# attiny_batsense.net
KiCad netlist of a schematic drawn in EAGLE
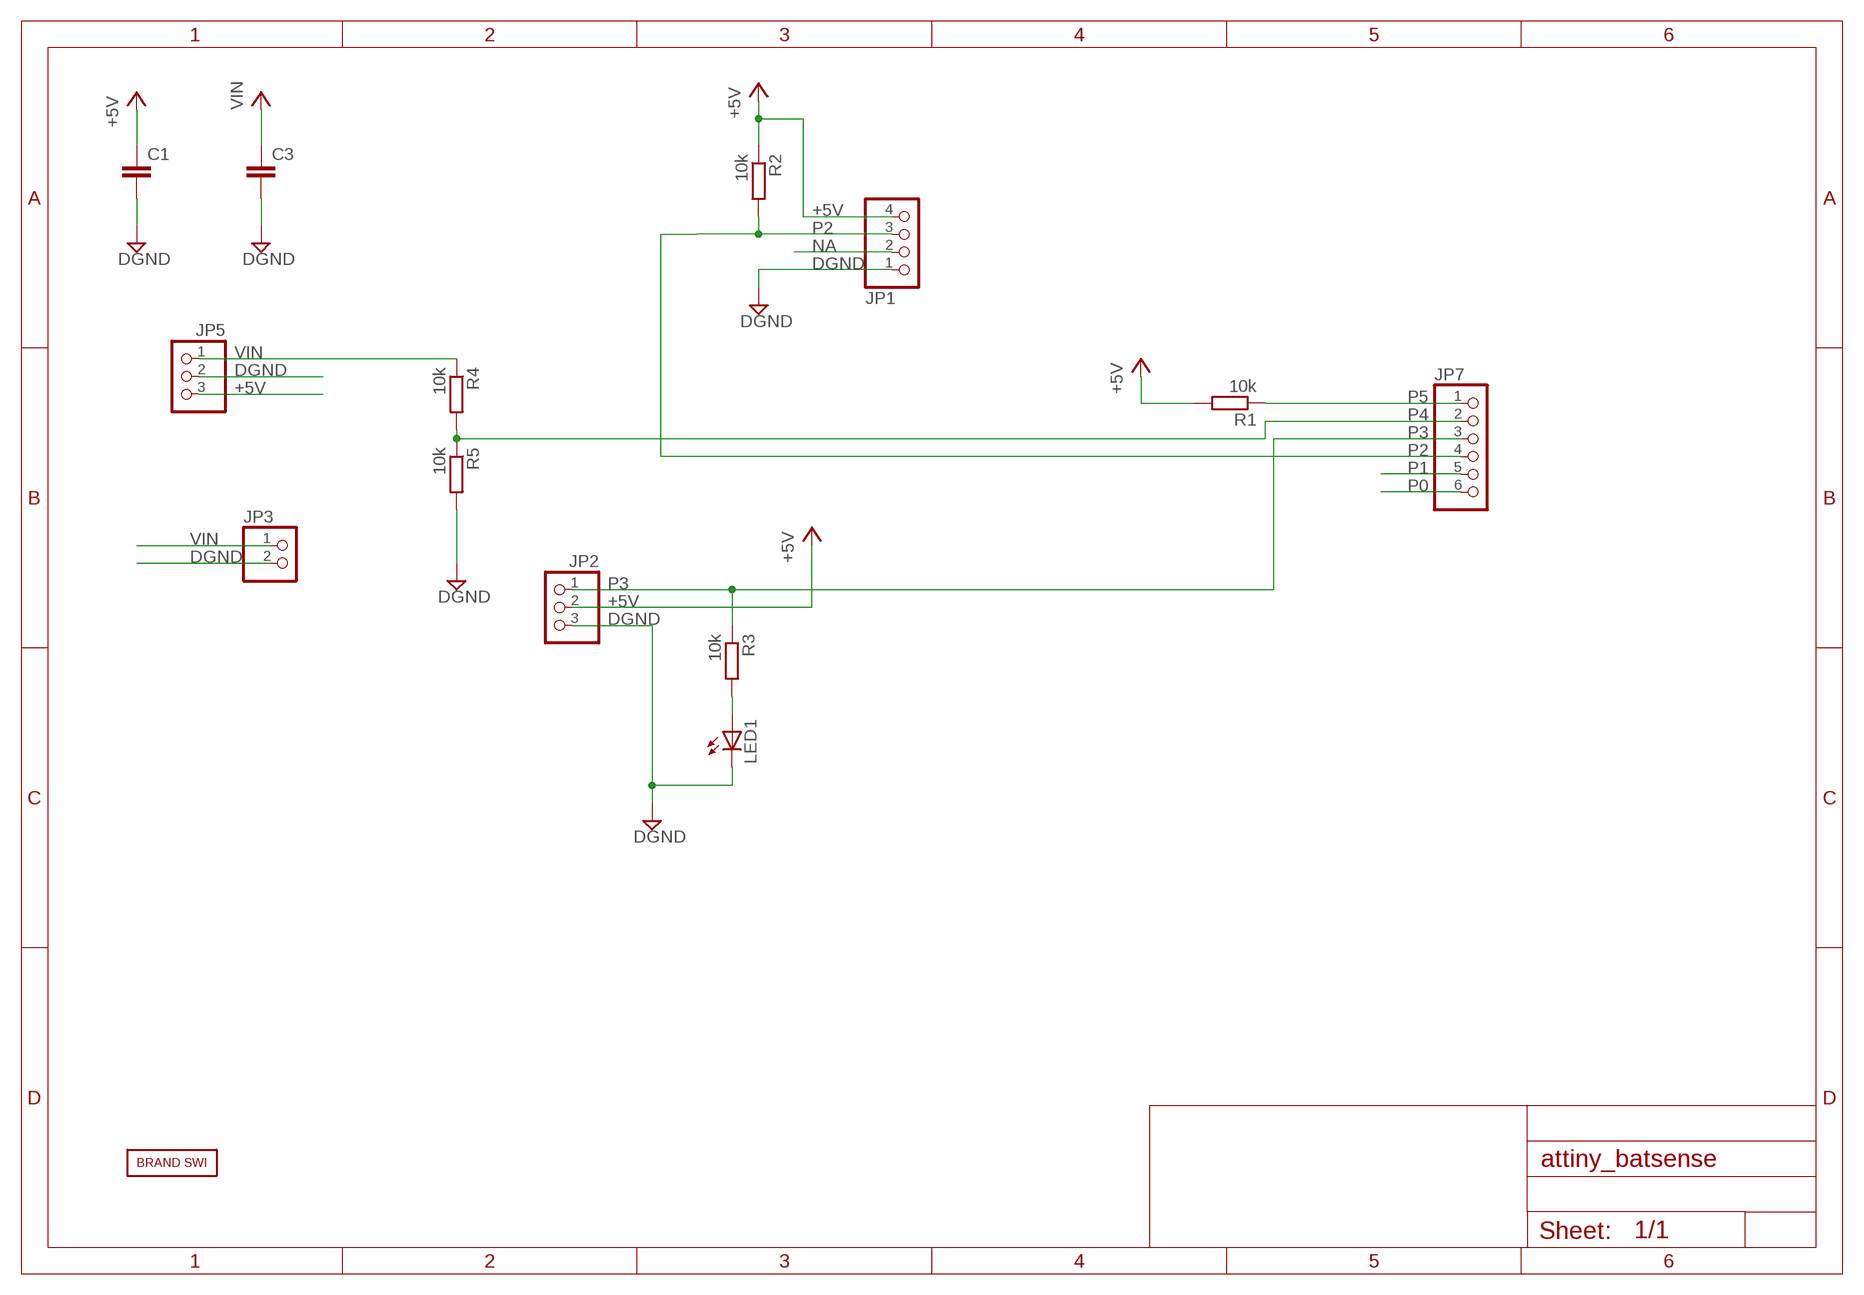
[diagram p0: schematic, sheet 1]

(export (version "E")
  (design (tool "Eeschema 10.0.6"))
  (components
    (comp (ref "C1")
      (value "C-EUC1210")
      (footprint "eagle-import:C1210")
      (libsource (lib "eagle-import") (part "C-EUC1210"))
    )
    (comp (ref "C3")
      (value "C-EUC1210")
      (footprint "eagle-import:C1210")
      (libsource (lib "eagle-import") (part "C-EUC1210"))
    )
    (comp (ref "JP1")
      (value "PINHD-1X4")
      (footprint "eagle-import:1X04")
      (libsource (lib "eagle-import") (part "PINHD-1X4"))
    )
    (comp (ref "JP2")
      (value "PINHD-1X3")
      (footprint "eagle-import:1X03")
      (libsource (lib "eagle-import") (part "PINHD-1X3"))
    )
    (comp (ref "JP3")
      (value "PINHD-1X2")
      (footprint "eagle-import:1X02")
      (libsource (lib "eagle-import") (part "PINHD-1X2"))
    )
    (comp (ref "JP5")
      (value "PINHD-1X3")
      (footprint "eagle-import:1X03")
      (libsource (lib "eagle-import") (part "PINHD-1X3"))
    )
    (comp (ref "JP7")
      (value "PINHD-1X6")
      (footprint "eagle-import:1X06")
      (libsource (lib "eagle-import") (part "PINHD-1X6"))
    )
    (comp (ref "LED1")
      (value "LED3MM")
      (footprint "eagle-import:LED3MM")
      (libsource (lib "eagle-import") (part "LED3MM"))
    )
    (comp (ref "R1")
      (value "10k")
      (footprint "eagle-import:R0805")
      (libsource (lib "eagle-import") (part "R-EU_R0805"))
    )
    (comp (ref "R2")
      (value "10k")
      (footprint "eagle-import:R0805")
      (libsource (lib "eagle-import") (part "R-EU_R0805"))
    )
    (comp (ref "R3")
      (value "10k")
      (footprint "eagle-import:R0805")
      (libsource (lib "eagle-import") (part "R-EU_R0805"))
    )
    (comp (ref "R4")
      (value "10k")
      (footprint "eagle-import:R0805")
      (libsource (lib "eagle-import") (part "R-EU_R0805"))
    )
    (comp (ref "R5")
      (value "10k")
      (footprint "eagle-import:R0805")
      (libsource (lib "eagle-import") (part "R-EU_R0805"))
    )
    (comp (ref "U$2")
      (value "BRAND_SWI5X7")
      (footprint "eagle-import:BRAND_SWI_5X7")
      (libsource (lib "eagle-import") (part "BRAND_SWI5X7"))
    )
  )
  (nets
    (net (code "1") (name "+5V") (class "Default")
      (node (ref "C1") (pin "1") (pinfunction "1_1") (pintype "passive"))
      (node (ref "JP1") (pin "4") (pinfunction "4_4") (pintype "passive"))
      (node (ref "JP2") (pin "2") (pinfunction "2_2") (pintype "passive"))
      (node (ref "JP5") (pin "3") (pinfunction "3_3") (pintype "passive"))
      (node (ref "R1") (pin "2") (pinfunction "2_2") (pintype "passive"))
      (node (ref "R2") (pin "1") (pinfunction "1_1") (pintype "passive"))
    )
    (net (code "2") (name "/NA") (class "Default")
      (node (ref "JP1") (pin "2") (pinfunction "2_2") (pintype "passive"))
    )
    (net (code "3") (name "/P0") (class "Default")
      (node (ref "JP7") (pin "6") (pinfunction "6_6") (pintype "passive"))
    )
    (net (code "4") (name "/P1") (class "Default")
      (node (ref "JP7") (pin "5") (pinfunction "5_5") (pintype "passive"))
    )
    (net (code "5") (name "/P2") (class "Default")
      (node (ref "JP1") (pin "3") (pinfunction "3_3") (pintype "passive"))
      (node (ref "JP7") (pin "4") (pinfunction "4_4") (pintype "passive"))
      (node (ref "R2") (pin "2") (pinfunction "2_2") (pintype "passive"))
    )
    (net (code "6") (name "/P3") (class "Default")
      (node (ref "JP2") (pin "1") (pinfunction "1_1") (pintype "passive"))
      (node (ref "JP7") (pin "3") (pinfunction "3_3") (pintype "passive"))
      (node (ref "R3") (pin "1") (pinfunction "1_1") (pintype "passive"))
    )
    (net (code "7") (name "/P4") (class "Default")
      (node (ref "JP7") (pin "2") (pinfunction "2_2") (pintype "passive"))
      (node (ref "R4") (pin "2") (pinfunction "2_2") (pintype "passive"))
      (node (ref "R5") (pin "1") (pinfunction "1_1") (pintype "passive"))
    )
    (net (code "8") (name "/P5") (class "Default")
      (node (ref "JP7") (pin "1") (pinfunction "1_1") (pintype "passive"))
      (node (ref "R1") (pin "1") (pinfunction "1_1") (pintype "passive"))
    )
    (net (code "9") (name "DGND") (class "Default")
      (node (ref "C1") (pin "2") (pinfunction "2_2") (pintype "passive"))
      (node (ref "C3") (pin "2") (pinfunction "2_2") (pintype "passive"))
      (node (ref "JP1") (pin "1") (pinfunction "1_1") (pintype "passive"))
      (node (ref "JP2") (pin "3") (pinfunction "3_3") (pintype "passive"))
      (node (ref "JP3") (pin "2") (pinfunction "2_2") (pintype "passive"))
      (node (ref "JP5") (pin "2") (pinfunction "2_2") (pintype "passive"))
      (node (ref "LED1") (pin "K") (pinfunction "C_K") (pintype "passive"))
      (node (ref "R5") (pin "2") (pinfunction "2_2") (pintype "passive"))
    )
    (net (code "10") (name "Net-(LED1-PadA)") (class "Default")
      (node (ref "LED1") (pin "A") (pinfunction "A_A") (pintype "passive"))
      (node (ref "R3") (pin "2") (pinfunction "2_2") (pintype "passive"))
    )
    (net (code "11") (name "VIN") (class "Default")
      (node (ref "C3") (pin "1") (pinfunction "1_1") (pintype "passive"))
      (node (ref "JP3") (pin "1") (pinfunction "1_1") (pintype "passive"))
      (node (ref "JP5") (pin "1") (pinfunction "1_1") (pintype "passive"))
      (node (ref "R4") (pin "1") (pinfunction "1_1") (pintype "passive"))
    )
  )
)
